# TLV320AIC23B_sch.net
KiCad netlist of a schematic drawn in Altium Designer
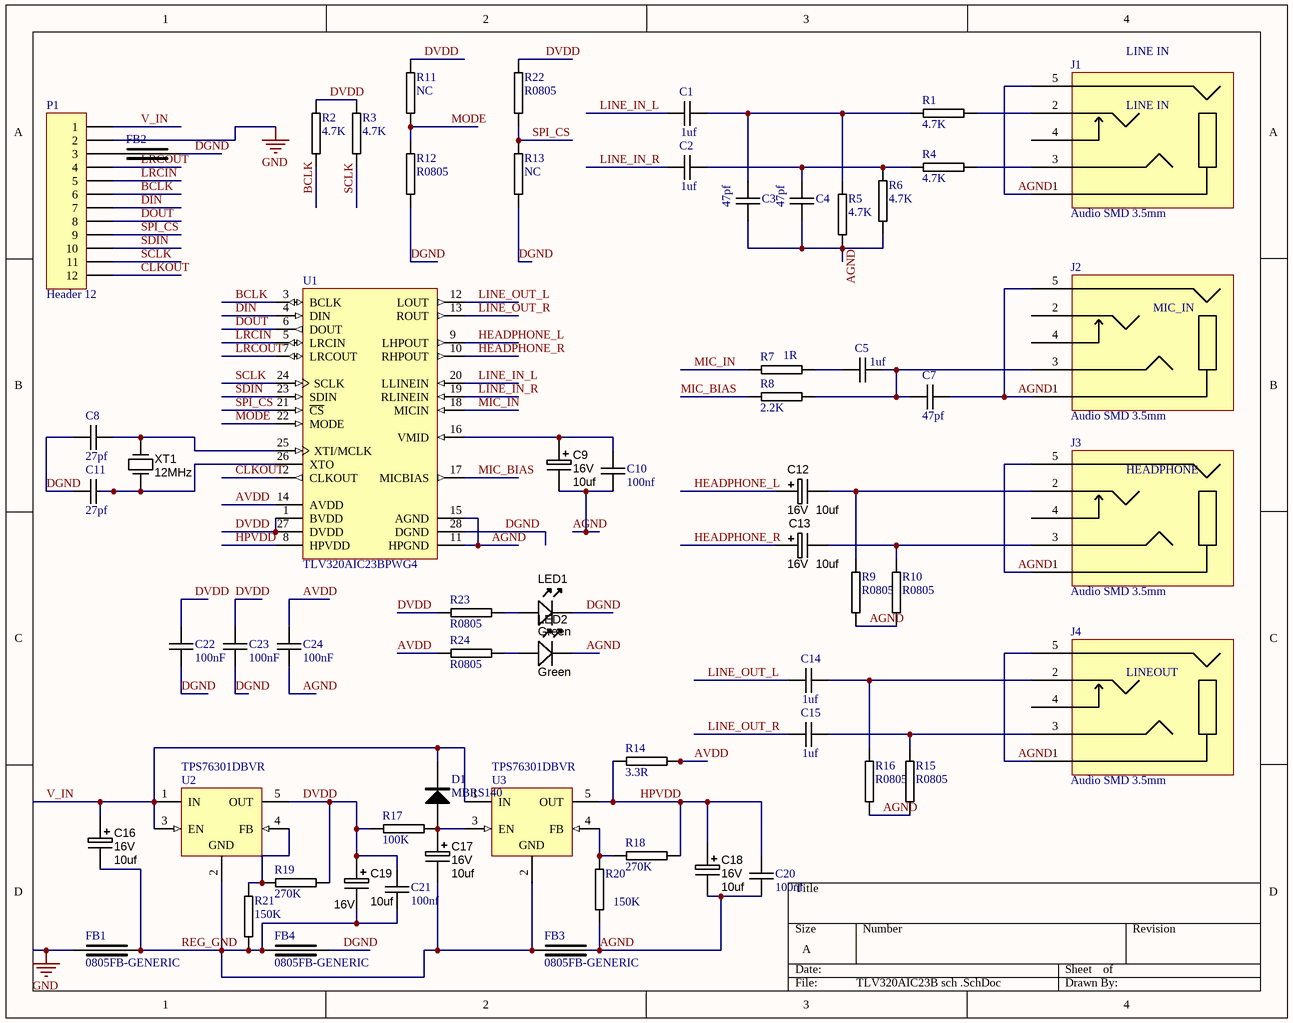
[diagram p0: TLV320AIC23B sch .SchDoc]

(export (version "E")
  (design (tool "Eeschema 10.0.6"))
  (components
    (comp (ref "C1")
      (value "1uf")
      (footprint "0805C-GENERIC")
      (description "GENERIC CAPACITOR NON POLARISED0603")
      (libsource (lib "Generic") (part "C0805-GENERIC"))
    )
    (comp (ref "C2")
      (value "1uf")
      (footprint "0805C-GENERIC")
      (description "GENERIC CAPACITOR NON POLARISED0603")
      (libsource (lib "Generic") (part "C0805-GENERIC"))
    )
    (comp (ref "C3")
      (value "47pf")
      (footprint "0805C-GENERIC")
      (description "GENERIC CAPACITOR NON POLARISED0603")
      (libsource (lib "Generic") (part "C0805-GENERIC"))
    )
    (comp (ref "C4")
      (value "47pf")
      (footprint "0805C-GENERIC")
      (description "GENERIC CAPACITOR NON POLARISED0603")
      (libsource (lib "Generic") (part "C0805-GENERIC"))
    )
    (comp (ref "C5")
      (value "1uf")
      (footprint "0805C-GENERIC")
      (description "GENERIC CAPACITOR NON POLARISED0603")
      (libsource (lib "Generic") (part "C0805-GENERIC"))
    )
    (comp (ref "C7")
      (value "47pf")
      (footprint "0805C-GENERIC")
      (description "GENERIC CAPACITOR NON POLARISED0603")
      (libsource (lib "Generic") (part "C0805-GENERIC"))
    )
    (comp (ref "C8")
      (value "27pf")
      (footprint "0805C-GENERIC")
      (description "GENERIC CAPACITOR NON POLARISED0603")
      (libsource (lib "Generic") (part "C0805-GENERIC"))
    )
    (comp (ref "C9")
      (value "10uf")
      (footprint "CAPMP3528X210N")
      (description "Capacitor SMD Tantalum 47uF 20% 6.3V 1210")
      (fields (field (name "TOLERANCE") "±20%") (field (name "RATINGS") "16V"))
      (libsource (lib "PBL - Capacitors") (part "CAPT_47u_1210_6V3"))
    )
    (comp (ref "C10")
      (value "100nf")
      (footprint "0805C-GENERIC")
      (description "GENERIC CAPACITOR NON POLARISED0603")
      (libsource (lib "Generic") (part "C0805-GENERIC"))
    )
    (comp (ref "C11")
      (value "27pf")
      (footprint "0805C-GENERIC")
      (description "GENERIC CAPACITOR NON POLARISED0603")
      (libsource (lib "Generic") (part "C0805-GENERIC"))
    )
    (comp (ref "C12")
      (value "10uf")
      (footprint "CAPMP3528X210N")
      (description "Capacitor SMD Tantalum 47uF 20% 6.3V 1210")
      (fields (field (name "TOLERANCE") "±20%") (field (name "RATINGS") "16V"))
      (libsource (lib "PBL - Capacitors") (part "CAPT_47u_1210_6V3"))
    )
    (comp (ref "C13")
      (value "10uf")
      (footprint "CAPMP3528X210N")
      (description "Capacitor SMD Tantalum 47uF 20% 6.3V 1210")
      (fields (field (name "TOLERANCE") "±20%") (field (name "RATINGS") "16V"))
      (libsource (lib "PBL - Capacitors") (part "CAPT_47u_1210_6V3"))
    )
    (comp (ref "C14")
      (value "1uf")
      (footprint "0805C-GENERIC")
      (description "GENERIC CAPACITOR NON POLARISED0603")
      (libsource (lib "Generic") (part "C0805-GENERIC"))
    )
    (comp (ref "C15")
      (value "1uf")
      (footprint "0805C-GENERIC")
      (description "GENERIC CAPACITOR NON POLARISED0603")
      (libsource (lib "Generic") (part "C0805-GENERIC"))
    )
    (comp (ref "C16")
      (value "10uf")
      (footprint "CAPMP3528X210N")
      (description "Capacitor SMD Tantalum 47uF 20% 6.3V 1210")
      (fields (field (name "TOLERANCE") "±20%") (field (name "RATINGS") "16V"))
      (libsource (lib "PBL - Capacitors") (part "CAPT_47u_1210_6V3"))
    )
    (comp (ref "C17")
      (value "10uf")
      (footprint "CAPMP3528X210N")
      (description "Capacitor SMD Tantalum 47uF 20% 6.3V 1210")
      (fields (field (name "TOLERANCE") "±20%") (field (name "RATINGS") "16V"))
      (libsource (lib "PBL - Capacitors") (part "CAPT_47u_1210_6V3"))
    )
    (comp (ref "C18")
      (value "10uf")
      (footprint "CAPMP3528X210N")
      (description "Capacitor SMD Tantalum 47uF 20% 6.3V 1210")
      (fields (field (name "TOLERANCE") "±20%") (field (name "RATINGS") "16V"))
      (libsource (lib "PBL - Capacitors") (part "CAPT_47u_1210_6V3"))
    )
    (comp (ref "C19")
      (value "10uf")
      (footprint "CAPMP3528X210N")
      (description "Capacitor SMD Tantalum 47uF 20% 6.3V 1210")
      (fields (field (name "TOLERANCE") "±20%") (field (name "RATINGS") "16V"))
      (libsource (lib "PBL - Capacitors") (part "CAPT_47u_1210_6V3"))
    )
    (comp (ref "C20")
      (value "100nf")
      (footprint "0805C-GENERIC")
      (description "GENERIC CAPACITOR NON POLARISED0603")
      (libsource (lib "Generic") (part "C0805-GENERIC"))
    )
    (comp (ref "C21")
      (value "100nf")
      (footprint "0805C-GENERIC")
      (description "GENERIC CAPACITOR NON POLARISED0603")
      (libsource (lib "Generic") (part "C0805-GENERIC"))
    )
    (comp (ref "C22")
      (value "100nF")
      (footprint "0603C-GENERIC")
      (description "CAPACITOR 0603 CERAMIC")
      (fields
        (field (name "MANUFACTURER PART NUMBER") "C1608X7R1E104K")
        (field (name "MANUFACTURER") "TDK Corporation")
      )
      (libsource (lib "Generic") (part "0603C-100NF-25V-X7R-TDK"))
    )
    (comp (ref "C23")
      (value "100nF")
      (footprint "0603C-GENERIC")
      (description "CAPACITOR 0603 CERAMIC")
      (fields
        (field (name "MANUFACTURER PART NUMBER") "C1608X7R1E104K")
        (field (name "MANUFACTURER") "TDK Corporation")
      )
      (libsource (lib "Generic") (part "0603C-100NF-25V-X7R-TDK"))
    )
    (comp (ref "C24")
      (value "100nF")
      (footprint "0603C-GENERIC")
      (description "CAPACITOR 0603 CERAMIC")
      (fields
        (field (name "MANUFACTURER PART NUMBER") "C1608X7R1E104K")
        (field (name "MANUFACTURER") "TDK Corporation")
      )
      (libsource (lib "Generic") (part "0603C-100NF-25V-X7R-TDK"))
    )
    (comp (ref "D1")
      (value "MBRS140")
      (footprint "DIODE-SMA")
      (description "DIODE")
      (libsource (lib "Generic") (part "MBRS140"))
    )
    (comp (ref "FB1")
      (value "0805FB-GENERIC")
      (footprint "0805FB-GENERIC")
      (description "FERRITE BEAD SMD")
      (libsource (lib "Generic") (part "0805FB-GENERIC"))
    )
    (comp (ref "FB2")
      (value "~")
      (footprint "0805FB-GENERIC")
      (description "FERRITE BEAD SMD")
      (libsource (lib "Generic") (part "0805FB-GENERIC"))
    )
    (comp (ref "FB3")
      (value "0805FB-GENERIC")
      (footprint "0805FB-GENERIC")
      (description "FERRITE BEAD SMD")
      (libsource (lib "Generic") (part "0805FB-GENERIC"))
    )
    (comp (ref "FB4")
      (value "0805FB-GENERIC")
      (footprint "0805FB-GENERIC")
      (description "FERRITE BEAD SMD")
      (libsource (lib "Generic") (part "0805FB-GENERIC"))
    )
    (comp (ref "J1")
      (value "Audio SMD 3.5mm")
      (footprint "SMDAudio3.5mm")
      (libsource (lib "Audio SMD 3.5mm") (part "Audio SMD 3.5mm"))
    )
    (comp (ref "J2")
      (value "Audio SMD 3.5mm")
      (footprint "SMDAudio3.5mm")
      (libsource (lib "Audio SMD 3.5mm") (part "Audio SMD 3.5mm"))
    )
    (comp (ref "J3")
      (value "Audio SMD 3.5mm")
      (footprint "SMDAudio3.5mm")
      (libsource (lib "Audio SMD 3.5mm") (part "Audio SMD 3.5mm"))
    )
    (comp (ref "J4")
      (value "Audio SMD 3.5mm")
      (footprint "SMDAudio3.5mm")
      (libsource (lib "Audio SMD 3.5mm") (part "Audio SMD 3.5mm"))
    )
    (comp (ref "LED1")
      (value "Green")
      (footprint "LED-0805-K")
      (description "LED, 0805 SMD, Green")
      (libsource (lib "PBL - Light Sources") (part "LED_SMD_Green_0805"))
    )
    (comp (ref "LED2")
      (value "Green")
      (footprint "LED-0805-K")
      (description "LED, 0805 SMD, Green")
      (libsource (lib "PBL - Light Sources") (part "LED_SMD_Green_0805"))
    )
    (comp (ref "P1")
      (value "Header 12")
      (footprint "HDR1X12")
      (description "Header, 12-Pin")
      (fields (field (name "PUBLISHER") "Altium Limited"))
      (libsource (lib "Miscellaneous Connectors") (part "Header 12"))
    )
    (comp (ref "R1")
      (value "4.7K")
      (footprint "0805R-GENERIC")
      (description "GENERIC RESISTOR 0805")
      (libsource (lib "Generic") (part "R0805-GENERIC"))
    )
    (comp (ref "R2")
      (value "4.7K")
      (footprint "0805R-GENERIC")
      (description "GENERIC RESISTOR 0805")
      (libsource (lib "Generic") (part "R0805-GENERIC"))
    )
    (comp (ref "R3")
      (value "4.7K")
      (footprint "0805R-GENERIC")
      (description "GENERIC RESISTOR 0805")
      (libsource (lib "Generic") (part "R0805-GENERIC"))
    )
    (comp (ref "R4")
      (value "4.7K")
      (footprint "0805R-GENERIC")
      (description "GENERIC RESISTOR 0805")
      (libsource (lib "Generic") (part "R0805-GENERIC"))
    )
    (comp (ref "R5")
      (value "4.7K")
      (footprint "0805R-GENERIC")
      (description "GENERIC RESISTOR 0805")
      (libsource (lib "Generic") (part "R0805-GENERIC"))
    )
    (comp (ref "R6")
      (value "4.7K")
      (footprint "0805R-GENERIC")
      (description "GENERIC RESISTOR 0805")
      (libsource (lib "Generic") (part "R0805-GENERIC"))
    )
    (comp (ref "R7")
      (value "1R")
      (footprint "0805R-GENERIC")
      (description "GENERIC RESISTOR 0805")
      (libsource (lib "Generic") (part "R0805-GENERIC"))
    )
    (comp (ref "R8")
      (value "2.2K")
      (footprint "0805R-GENERIC")
      (description "GENERIC RESISTOR 0805")
      (libsource (lib "Generic") (part "R0805-GENERIC"))
    )
    (comp (ref "R9")
      (value "R0805")
      (footprint "0805R-GENERIC")
      (description "GENERIC RESISTOR 0805")
      (libsource (lib "Generic") (part "R0805-GENERIC"))
    )
    (comp (ref "R10")
      (value "R0805")
      (footprint "0805R-GENERIC")
      (description "GENERIC RESISTOR 0805")
      (libsource (lib "Generic") (part "R0805-GENERIC"))
    )
    (comp (ref "R11")
      (value "NC")
      (footprint "0805R-GENERIC")
      (description "GENERIC RESISTOR 0805")
      (libsource (lib "Generic") (part "R0805-GENERIC"))
    )
    (comp (ref "R12")
      (value "R0805")
      (footprint "0805R-GENERIC")
      (description "GENERIC RESISTOR 0805")
      (libsource (lib "Generic") (part "R0805-GENERIC"))
    )
    (comp (ref "R13")
      (value "NC")
      (footprint "0805R-GENERIC")
      (description "GENERIC RESISTOR 0805")
      (libsource (lib "Generic") (part "R0805-GENERIC"))
    )
    (comp (ref "R14")
      (value "3.3R")
      (footprint "0805R-GENERIC")
      (description "GENERIC RESISTOR 0805")
      (libsource (lib "Generic") (part "R0805-GENERIC"))
    )
    (comp (ref "R15")
      (value "R0805")
      (footprint "0805R-GENERIC")
      (description "GENERIC RESISTOR 0805")
      (libsource (lib "Generic") (part "R0805-GENERIC"))
    )
    (comp (ref "R16")
      (value "R0805")
      (footprint "0805R-GENERIC")
      (description "GENERIC RESISTOR 0805")
      (libsource (lib "Generic") (part "R0805-GENERIC"))
    )
    (comp (ref "R17")
      (value "100K")
      (footprint "0805R-GENERIC")
      (description "GENERIC RESISTOR 0805")
      (libsource (lib "Generic") (part "R0805-GENERIC"))
    )
    (comp (ref "R18")
      (value "270K")
      (footprint "0805R-GENERIC")
      (description "GENERIC RESISTOR 0805")
      (libsource (lib "Generic") (part "R0805-GENERIC"))
    )
    (comp (ref "R19")
      (value "270K")
      (footprint "0805R-GENERIC")
      (description "GENERIC RESISTOR 0805")
      (libsource (lib "Generic") (part "R0805-GENERIC"))
    )
    (comp (ref "R20")
      (value "150K")
      (footprint "0805R-GENERIC")
      (description "GENERIC RESISTOR 0805")
      (libsource (lib "Generic") (part "R0805-GENERIC"))
    )
    (comp (ref "R21")
      (value "150K")
      (footprint "0805R-GENERIC")
      (description "GENERIC RESISTOR 0805")
      (libsource (lib "Generic") (part "R0805-GENERIC"))
    )
    (comp (ref "R22")
      (value "R0805")
      (footprint "0805R-GENERIC")
      (description "GENERIC RESISTOR 0805")
      (libsource (lib "Generic") (part "R0805-GENERIC"))
    )
    (comp (ref "R23")
      (value "R0805")
      (footprint "0805R-GENERIC")
      (description "GENERIC RESISTOR 0805")
      (libsource (lib "Generic") (part "R0805-GENERIC"))
    )
    (comp (ref "R24")
      (value "R0805")
      (footprint "0805R-GENERIC")
      (description "GENERIC RESISTOR 0805")
      (libsource (lib "Generic") (part "R0805-GENERIC"))
    )
    (comp (ref "U1")
      (value "TLV320AIC23BPWG4")
      (footprint "PW28_N")
      (fields (field (name "MANUFACTURER") "Texas Instruments"))
      (libsource (lib "TI Audio CODEC") (part "TLV320AIC23BPWG4"))
    )
    (comp (ref "U2")
      (value "TPS76301DBVR")
      (footprint "TI-DBV5_N")
      (fields (field (name "MANUFACTURER") "Texas Instruments"))
      (libsource (lib "TI Power Management Linear Regulator Single Channel LDO (0-350mA)") (part "TPS76301DBVR"))
    )
    (comp (ref "U3")
      (value "TPS76301DBVR")
      (footprint "TI-DBV5_N")
      (fields (field (name "MANUFACTURER") "Texas Instruments"))
      (libsource (lib "TI Power Management Linear Regulator Single Channel LDO (0-350mA)") (part "TPS76301DBVR"))
    )
    (comp (ref "XT1")
      (value "12MHz")
      (footprint "CRYSTAL_HC49-US-SM")
      (description "Resonator Ceramic 6.00 MHz 30ppm")
      (libsource (lib "PBL - Resonators") (part "Crystal_6MHz_HC49/US"))
    )
  )
  (nets
    (net (code "1") (name "/AGND") (class "Default")
      (node (ref "C10") (pin "2") (pintype "passive"))
      (node (ref "C18") (pin "2") (pintype "passive"))
      (node (ref "C20") (pin "2") (pintype "passive"))
      (node (ref "C24") (pin "2") (pintype "passive"))
      (node (ref "C3") (pin "1") (pintype "passive"))
      (node (ref "C4") (pin "1") (pintype "passive"))
      (node (ref "C7") (pin "1") (pintype "passive"))
      (node (ref "C9") (pin "2") (pintype "passive"))
      (node (ref "FB3") (pin "2") (pintype "passive"))
      (node (ref "J1") (pin "1") (pinfunction "1_1") (pintype "power_in"))
      (node (ref "J1") (pin "5") (pinfunction "5_5") (pintype "power_in"))
      (node (ref "J2") (pin "1") (pinfunction "1_1") (pintype "power_in"))
      (node (ref "J2") (pin "5") (pinfunction "5_5") (pintype "power_in"))
      (node (ref "J3") (pin "1") (pinfunction "1_1") (pintype "power_in"))
      (node (ref "J3") (pin "5") (pinfunction "5_5") (pintype "power_in"))
      (node (ref "J4") (pin "1") (pinfunction "1_1") (pintype "power_in"))
      (node (ref "J4") (pin "5") (pinfunction "5_5") (pintype "power_in"))
      (node (ref "LED2") (pin "K") (pinfunction "K_K") (pintype "passive"))
      (node (ref "R10") (pin "1") (pintype "passive"))
      (node (ref "R15") (pin "1") (pintype "passive"))
      (node (ref "R16") (pin "1") (pintype "passive"))
      (node (ref "R20") (pin "1") (pintype "passive"))
      (node (ref "R5") (pin "1") (pintype "passive"))
      (node (ref "R6") (pin "1") (pintype "passive"))
      (node (ref "R9") (pin "1") (pintype "passive"))
      (node (ref "U1") (pin "11") (pinfunction "HPGND_11") (pintype "power_in"))
      (node (ref "U1") (pin "15") (pinfunction "AGND_15") (pintype "power_in"))
    )
    (net (code "2") (name "/AVDD") (class "Default")
      (node (ref "C24") (pin "1") (pintype "passive"))
      (node (ref "R14") (pin "2") (pintype "passive"))
      (node (ref "R24") (pin "2") (pintype "passive"))
      (node (ref "U1") (pin "14") (pinfunction "AVDD_14") (pintype "power_in"))
    )
    (net (code "3") (name "/BCLK") (class "Default")
      (node (ref "P1") (pin "6") (pinfunction "6_6") (pintype "passive"))
      (node (ref "R2") (pin "1") (pintype "passive"))
      (node (ref "U1") (pin "3") (pinfunction "BCLK_3") (pintype "bidirectional"))
    )
    (net (code "4") (name "/CLKOUT") (class "Default")
      (node (ref "P1") (pin "12") (pinfunction "12_12") (pintype "passive"))
      (node (ref "U1") (pin "2") (pinfunction "CLKOUT_2") (pintype "output"))
    )
    (net (code "5") (name "/DGND") (class "Default")
      (node (ref "C11") (pin "2") (pintype "passive"))
      (node (ref "C22") (pin "2") (pintype "passive"))
      (node (ref "C23") (pin "2") (pintype "passive"))
      (node (ref "C8") (pin "1") (pintype "passive"))
      (node (ref "FB2") (pin "2") (pintype "passive"))
      (node (ref "FB4") (pin "2") (pintype "passive"))
      (node (ref "LED1") (pin "K") (pinfunction "K_K") (pintype "passive"))
      (node (ref "R12") (pin "1") (pintype "passive"))
      (node (ref "R13") (pin "1") (pintype "passive"))
      (node (ref "U1") (pin "28") (pinfunction "DGND_28") (pintype "power_in"))
    )
    (net (code "6") (name "/DIN") (class "Default")
      (node (ref "P1") (pin "7") (pinfunction "7_7") (pintype "passive"))
      (node (ref "U1") (pin "4") (pinfunction "DIN_4") (pintype "input"))
    )
    (net (code "7") (name "/DOUT") (class "Default")
      (node (ref "P1") (pin "8") (pinfunction "8_8") (pintype "passive"))
      (node (ref "U1") (pin "6") (pinfunction "DOUT_6") (pintype "output"))
    )
    (net (code "8") (name "/DVDD") (class "Default")
      (node (ref "C19") (pin "1") (pintype "passive"))
      (node (ref "C21") (pin "1") (pintype "passive"))
      (node (ref "C22") (pin "1") (pintype "passive"))
      (node (ref "C23") (pin "1") (pintype "passive"))
      (node (ref "R11") (pin "2") (pintype "passive"))
      (node (ref "R17") (pin "1") (pintype "passive"))
      (node (ref "R19") (pin "1") (pintype "passive"))
      (node (ref "R2") (pin "2") (pintype "passive"))
      (node (ref "R22") (pin "2") (pintype "passive"))
      (node (ref "R23") (pin "2") (pintype "passive"))
      (node (ref "R3") (pin "2") (pintype "passive"))
      (node (ref "U1") (pin "1") (pinfunction "BVDD_1") (pintype "power_in"))
      (node (ref "U1") (pin "27") (pinfunction "DVDD_27") (pintype "power_in"))
      (node (ref "U2") (pin "5") (pinfunction "OUT_5") (pintype "power_in"))
    )
    (net (code "9") (name "/HEADPHONE_L") (class "Default")
      (node (ref "C12") (pin "1") (pintype "passive"))
      (node (ref "U1") (pin "9") (pinfunction "LHPOUT_9") (pintype "output"))
    )
    (net (code "10") (name "/HEADPHONE_R") (class "Default")
      (node (ref "C13") (pin "1") (pintype "passive"))
      (node (ref "U1") (pin "10") (pinfunction "RHPOUT_10") (pintype "output"))
    )
    (net (code "11") (name "/HPVDD") (class "Default")
      (node (ref "C18") (pin "1") (pintype "passive"))
      (node (ref "C20") (pin "1") (pintype "passive"))
      (node (ref "R14") (pin "1") (pintype "passive"))
      (node (ref "R18") (pin "1") (pintype "passive"))
      (node (ref "U1") (pin "8") (pinfunction "HPVDD_8") (pintype "power_in"))
      (node (ref "U3") (pin "5") (pinfunction "OUT_5") (pintype "power_in"))
    )
    (net (code "12") (name "/LINE_IN_L") (class "Default")
      (node (ref "C1") (pin "1") (pintype "passive"))
      (node (ref "U1") (pin "20") (pinfunction "LLINEIN_20") (pintype "input"))
    )
    (net (code "13") (name "/LINE_IN_R") (class "Default")
      (node (ref "C2") (pin "1") (pintype "passive"))
      (node (ref "U1") (pin "19") (pinfunction "RLINEIN_19") (pintype "input"))
    )
    (net (code "14") (name "/LINE_OUT_L") (class "Default")
      (node (ref "C14") (pin "2") (pintype "passive"))
      (node (ref "U1") (pin "12") (pinfunction "LOUT_12") (pintype "output"))
    )
    (net (code "15") (name "/LINE_OUT_R") (class "Default")
      (node (ref "C15") (pin "2") (pintype "passive"))
      (node (ref "U1") (pin "13") (pinfunction "ROUT_13") (pintype "output"))
    )
    (net (code "16") (name "/LRCIN") (class "Default")
      (node (ref "P1") (pin "5") (pinfunction "5_5") (pintype "passive"))
      (node (ref "U1") (pin "5") (pinfunction "LRCIN_5") (pintype "bidirectional"))
    )
    (net (code "17") (name "/LRCOUT") (class "Default")
      (node (ref "P1") (pin "4") (pinfunction "4_4") (pintype "passive"))
      (node (ref "U1") (pin "7") (pinfunction "LRCOUT_7") (pintype "bidirectional"))
    )
    (net (code "18") (name "/MIC_BIAS") (class "Default")
      (node (ref "R8") (pin "1") (pintype "passive"))
      (node (ref "U1") (pin "17") (pinfunction "MICBIAS_17") (pintype "output"))
    )
    (net (code "19") (name "/MIC_IN") (class "Default")
      (node (ref "R7") (pin "1") (pintype "passive"))
      (node (ref "U1") (pin "18") (pinfunction "MICIN_18") (pintype "input"))
    )
    (net (code "20") (name "/MODE") (class "Default")
      (node (ref "R11") (pin "1") (pintype "passive"))
      (node (ref "R12") (pin "2") (pintype "passive"))
      (node (ref "U1") (pin "22") (pinfunction "MODE_22") (pintype "input"))
    )
    (net (code "21") (name "/REG_GND") (class "Default")
      (node (ref "C16") (pin "2") (pintype "passive"))
      (node (ref "C17") (pin "2") (pintype "passive"))
      (node (ref "C19") (pin "2") (pintype "passive"))
      (node (ref "C21") (pin "2") (pintype "passive"))
      (node (ref "FB1") (pin "2") (pintype "passive"))
      (node (ref "FB3") (pin "1") (pintype "passive"))
      (node (ref "FB4") (pin "1") (pintype "passive"))
      (node (ref "R21") (pin "1") (pintype "passive"))
      (node (ref "U2") (pin "2") (pinfunction "GND_2") (pintype "power_in"))
      (node (ref "U3") (pin "2") (pinfunction "GND_2") (pintype "power_in"))
    )
    (net (code "22") (name "/SCLK") (class "Default")
      (node (ref "P1") (pin "11") (pinfunction "11_11") (pintype "passive"))
      (node (ref "R3") (pin "1") (pintype "passive"))
      (node (ref "U1") (pin "24") (pinfunction "SCLK_24") (pintype "input"))
    )
    (net (code "23") (name "/SDIN") (class "Default")
      (node (ref "P1") (pin "10") (pinfunction "10_10") (pintype "passive"))
      (node (ref "U1") (pin "23") (pinfunction "SDIN_23") (pintype "input"))
    )
    (net (code "24") (name "/SPI_CS") (class "Default")
      (node (ref "P1") (pin "9") (pinfunction "9_9") (pintype "passive"))
      (node (ref "R13") (pin "2") (pintype "passive"))
      (node (ref "R22") (pin "1") (pintype "passive"))
      (node (ref "U1") (pin "21") (pinfunction "~{CS}_21") (pintype "input"))
    )
    (net (code "25") (name "/V_IN") (class "Default")
      (node (ref "C16") (pin "1") (pintype "passive"))
      (node (ref "D1") (pin "K") (pinfunction "K_K") (pintype "passive"))
      (node (ref "P1") (pin "1") (pinfunction "1_1") (pintype "passive"))
      (node (ref "U2") (pin "1") (pinfunction "IN_1") (pintype "power_in"))
      (node (ref "U2") (pin "3") (pinfunction "EN_3") (pintype "input"))
      (node (ref "U3") (pin "1") (pinfunction "IN_1") (pintype "power_in"))
    )
    (net (code "26") (name "GND") (class "Default")
      (node (ref "FB1") (pin "1") (pintype "passive"))
      (node (ref "P1") (pin "2") (pinfunction "2_2") (pintype "passive"))
    )
    (net (code "27") (name "Net-(C1-Pad2)") (class "Default")
      (node (ref "C1") (pin "2") (pintype "passive"))
      (node (ref "C3") (pin "2") (pintype "passive"))
      (node (ref "R1") (pin "1") (pintype "passive"))
      (node (ref "R5") (pin "2") (pintype "passive"))
    )
    (net (code "28") (name "Net-(C2-Pad2)") (class "Default")
      (node (ref "C2") (pin "2") (pintype "passive"))
      (node (ref "C4") (pin "2") (pintype "passive"))
      (node (ref "R4") (pin "1") (pintype "passive"))
      (node (ref "R6") (pin "2") (pintype "passive"))
    )
    (net (code "29") (name "Net-(C5-Pad1)") (class "Default")
      (node (ref "C5") (pin "1") (pintype "passive"))
      (node (ref "C7") (pin "2") (pintype "passive"))
      (node (ref "J2") (pin "3") (pinfunction "3_3") (pintype "power_in"))
      (node (ref "R8") (pin "2") (pintype "passive"))
    )
    (net (code "30") (name "Net-(C5-Pad2)") (class "Default")
      (node (ref "C5") (pin "2") (pintype "passive"))
      (node (ref "R7") (pin "2") (pintype "passive"))
    )
    (net (code "31") (name "Net-(C12-Pad2)") (class "Default")
      (node (ref "C12") (pin "2") (pintype "passive"))
      (node (ref "J3") (pin "2") (pinfunction "2_2") (pintype "power_in"))
      (node (ref "R9") (pin "2") (pintype "passive"))
    )
    (net (code "32") (name "Net-(C13-Pad2)") (class "Default")
      (node (ref "C13") (pin "2") (pintype "passive"))
      (node (ref "J3") (pin "3") (pinfunction "3_3") (pintype "power_in"))
      (node (ref "R10") (pin "2") (pintype "passive"))
    )
    (net (code "33") (name "Net-(C14-Pad1)") (class "Default")
      (node (ref "C14") (pin "1") (pintype "passive"))
      (node (ref "J4") (pin "2") (pinfunction "2_2") (pintype "power_in"))
      (node (ref "R16") (pin "2") (pintype "passive"))
    )
    (net (code "34") (name "Net-(C15-Pad1)") (class "Default")
      (node (ref "C15") (pin "1") (pintype "passive"))
      (node (ref "J4") (pin "3") (pinfunction "3_3") (pintype "power_in"))
      (node (ref "R15") (pin "2") (pintype "passive"))
    )
    (net (code "35") (name "Net-(FB2-Pad1)") (class "Default")
      (node (ref "FB2") (pin "1") (pintype "passive"))
      (node (ref "P1") (pin "3") (pinfunction "3_3") (pintype "passive"))
    )
    (net (code "36") (name "Net-(J1-Pad2)") (class "Default")
      (node (ref "J1") (pin "2") (pinfunction "2_2") (pintype "power_in"))
      (node (ref "R1") (pin "2") (pintype "passive"))
    )
    (net (code "37") (name "Net-(J1-Pad3)") (class "Default")
      (node (ref "J1") (pin "3") (pinfunction "3_3") (pintype "power_in"))
      (node (ref "R4") (pin "2") (pintype "passive"))
    )
    (net (code "38") (name "Net-(LED1-PadA)") (class "Default")
      (node (ref "LED1") (pin "A") (pinfunction "A_A") (pintype "passive"))
      (node (ref "R23") (pin "1") (pintype "passive"))
    )
    (net (code "39") (name "Net-(LED2-PadA)") (class "Default")
      (node (ref "LED2") (pin "A") (pinfunction "A_A") (pintype "passive"))
      (node (ref "R24") (pin "1") (pintype "passive"))
    )
    (net (code "40") (name "Net-(U1-VMID)") (class "Default")
      (node (ref "C10") (pin "1") (pintype "passive"))
      (node (ref "C9") (pin "1") (pintype "passive"))
      (node (ref "U1") (pin "16") (pinfunction "VMID_16") (pintype "input"))
    )
    (net (code "41") (name "Net-(U1-XTI{slash}MCLK)") (class "Default")
      (node (ref "C8") (pin "2") (pintype "passive"))
      (node (ref "U1") (pin "25") (pinfunction "XTI/MCLK_25") (pintype "input"))
      (node (ref "XT1") (pin "2") (pinfunction "OUT_2") (pintype "passive"))
    )
    (net (code "42") (name "Net-(U1-XTO)") (class "Default")
      (node (ref "C11") (pin "1") (pintype "passive"))
      (node (ref "U1") (pin "26") (pinfunction "XTO_26") (pintype "passive"))
      (node (ref "XT1") (pin "1") (pinfunction "IN_1") (pintype "passive"))
    )
    (net (code "43") (name "Net-(U2-FB)") (class "Default")
      (node (ref "R19") (pin "2") (pintype "passive"))
      (node (ref "R21") (pin "2") (pintype "passive"))
      (node (ref "U2") (pin "4") (pinfunction "FB_4") (pintype "input"))
    )
    (net (code "44") (name "Net-(U3-EN)") (class "Default")
      (node (ref "C17") (pin "1") (pintype "passive"))
      (node (ref "D1") (pin "A") (pinfunction "A_A") (pintype "passive"))
      (node (ref "R17") (pin "2") (pintype "passive"))
      (node (ref "U3") (pin "3") (pinfunction "EN_3") (pintype "input"))
    )
    (net (code "45") (name "Net-(U3-FB)") (class "Default")
      (node (ref "R18") (pin "2") (pintype "passive"))
      (node (ref "R20") (pin "2") (pintype "passive"))
      (node (ref "U3") (pin "4") (pinfunction "FB_4") (pintype "input"))
    )
    (net (code "46") (name "unconnected-(J1-Pad4)") (class "Default")
      (node (ref "J1") (pin "4") (pinfunction "4_4") (pintype "power_in"))
    )
    (net (code "47") (name "unconnected-(J2-Pad2)") (class "Default")
      (node (ref "J2") (pin "2") (pinfunction "2_2") (pintype "power_in"))
    )
    (net (code "48") (name "unconnected-(J2-Pad4)") (class "Default")
      (node (ref "J2") (pin "4") (pinfunction "4_4") (pintype "power_in"))
    )
    (net (code "49") (name "unconnected-(J3-Pad4)") (class "Default")
      (node (ref "J3") (pin "4") (pinfunction "4_4") (pintype "power_in"))
    )
    (net (code "50") (name "unconnected-(J4-Pad4)") (class "Default")
      (node (ref "J4") (pin "4") (pinfunction "4_4") (pintype "power_in"))
    )
  )
)
